# EZ_FX3USB.net
KiCad netlist of a schematic drawn in Altium Designer
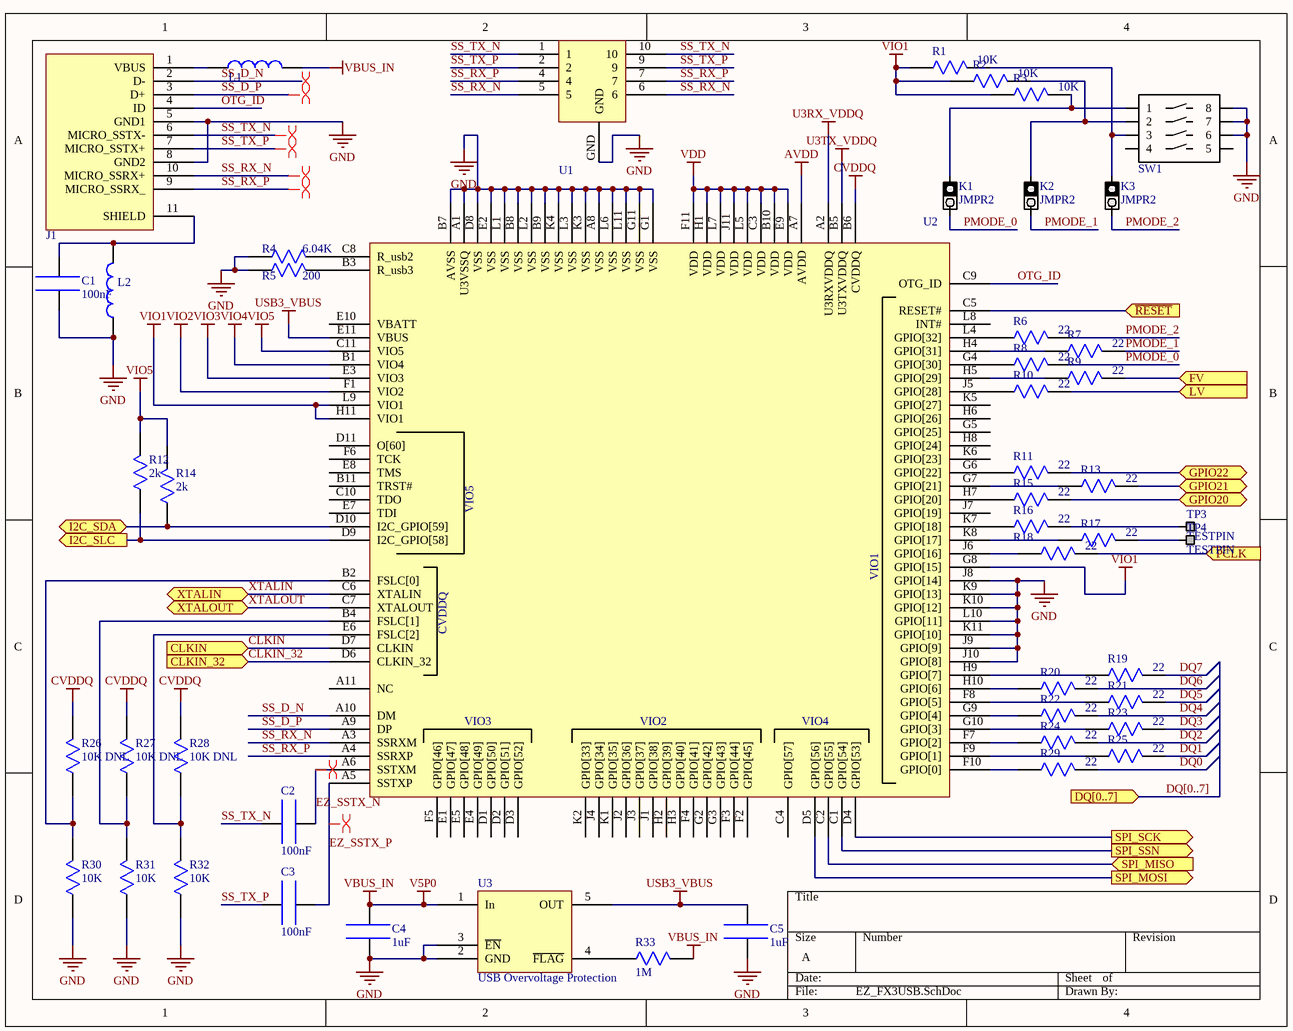
[diagram p0: EZ_FX3USB.SchDoc]

(export (version "E")
  (design (tool "Eeschema 10.0.6"))
  (components
    (comp (ref "C1")
      (value "100nF")
      (footprint "SMD Capacitor 0603")
      (fields (field (name "Comment") "Capacitor"))
      (libsource (lib "DA_Component_Library") (part "Capacitor"))
    )
    (comp (ref "C2")
      (value "100nF")
      (footprint "SMD Capacitor 0603")
      (fields (field (name "Comment") "Capacitor"))
      (libsource (lib "DA_Component_Library") (part "Capacitor"))
    )
    (comp (ref "C3")
      (value "100nF")
      (footprint "SMD Capacitor 0603")
      (fields (field (name "Comment") "Capacitor"))
      (libsource (lib "DA_Component_Library") (part "Capacitor"))
    )
    (comp (ref "C4")
      (value "1uF")
      (footprint "SMD Capacitor 0603")
      (fields (field (name "Comment") "Capacitor"))
      (libsource (lib "DA_Component_Library") (part "Capacitor"))
    )
    (comp (ref "C5")
      (value "1uF")
      (footprint "SMD Capacitor 0603")
      (fields (field (name "Comment") "Capacitor"))
      (libsource (lib "DA_Component_Library") (part "Capacitor"))
    )
    (comp (ref "J1")
      (value "USB3 MicroB")
      (footprint "PCBComponent_1")
      (libsource (lib "DA_Component_Library") (part "USB3 MicroB"))
    )
    (comp (ref "K1")
      (value "JMPR2")
      (footprint "JMPR2")
      (description "JMPR2 OPEN BY DEFAULT")
      (fields
        (field (name "MANUFACTURER") "Sullins Connector Solutions")
        (field (name "MANUFACTURER PART NUMBER") "PBC36SAAN")
      )
      (libsource (lib "vh_altium_library") (part "JMPR2"))
    )
    (comp (ref "K2")
      (value "JMPR2")
      (footprint "JMPR2")
      (description "JMPR2 OPEN BY DEFAULT")
      (fields
        (field (name "MANUFACTURER") "Sullins Connector Solutions")
        (field (name "MANUFACTURER PART NUMBER") "PBC36SAAN")
      )
      (libsource (lib "vh_altium_library") (part "JMPR2"))
    )
    (comp (ref "K3")
      (value "JMPR2")
      (footprint "JMPR2")
      (description "JMPR2 OPEN BY DEFAULT")
      (fields
        (field (name "MANUFACTURER") "Sullins Connector Solutions")
        (field (name "MANUFACTURER PART NUMBER") "PBC36SAAN")
      )
      (libsource (lib "vh_altium_library") (part "JMPR2"))
    )
    (comp (ref "L1")
      (value "Ferrite Bead")
      (footprint "BLM21PG221SN1D_0805")
      (libsource (lib "DA_Component_Library") (part "Ferrite Bead"))
    )
    (comp (ref "L2")
      (value "Ferrite Bead")
      (footprint "BLM21PG221SN1D_0805")
      (libsource (lib "DA_Component_Library") (part "Ferrite Bead"))
    )
    (comp (ref "R1")
      (value "10K")
      (footprint "SMD Resistor 0603")
      (libsource (lib "DA_Component_Library") (part "Resistor"))
    )
    (comp (ref "R2")
      (value "10K")
      (footprint "SMD Resistor 0603")
      (fields (field (name "Comment") "Resistor"))
      (libsource (lib "DA_Component_Library") (part "Resistor"))
    )
    (comp (ref "R3")
      (value "10K")
      (footprint "SMD Resistor 0603")
      (fields (field (name "Comment") "Resistor"))
      (libsource (lib "DA_Component_Library") (part "Resistor"))
    )
    (comp (ref "R4")
      (value "6.04K")
      (footprint "SMD Resistor 0603")
      (fields (field (name "Comment") "Resistor"))
      (libsource (lib "DA_Component_Library") (part "Resistor"))
    )
    (comp (ref "R5")
      (value "200")
      (footprint "SMD Resistor 0603")
      (fields (field (name "Comment") "Resistor"))
      (libsource (lib "DA_Component_Library") (part "Resistor"))
    )
    (comp (ref "R6")
      (value "22")
      (footprint "SMD Resistor 0603")
      (fields (field (name "Comment") "\"=Value\""))
      (libsource (lib "DA_Component_Library") (part "Resistor"))
    )
    (comp (ref "R7")
      (value "22")
      (footprint "SMD Resistor 0603")
      (fields (field (name "Comment") "Resistor"))
      (libsource (lib "DA_Component_Library") (part "Resistor"))
    )
    (comp (ref "R8")
      (value "22")
      (footprint "SMD Resistor 0603")
      (fields (field (name "Comment") "Resistor"))
      (libsource (lib "DA_Component_Library") (part "Resistor"))
    )
    (comp (ref "R9")
      (value "22")
      (footprint "SMD Resistor 0603")
      (fields (field (name "Comment") "Resistor"))
      (libsource (lib "DA_Component_Library") (part "Resistor"))
    )
    (comp (ref "R10")
      (value "22")
      (footprint "SMD Resistor 0603")
      (fields (field (name "Comment") "Resistor"))
      (libsource (lib "DA_Component_Library") (part "Resistor"))
    )
    (comp (ref "R11")
      (value "22")
      (footprint "SMD Resistor 0603")
      (fields (field (name "Comment") "Resistor"))
      (libsource (lib "DA_Component_Library") (part "Resistor"))
    )
    (comp (ref "R12")
      (value "2k")
      (footprint "SMD Resistor 0603")
      (fields (field (name "Comment") "Resistor"))
      (libsource (lib "DA_Component_Library") (part "Resistor"))
    )
    (comp (ref "R13")
      (value "22")
      (footprint "SMD Resistor 0603")
      (fields (field (name "Comment") "Resistor"))
      (libsource (lib "DA_Component_Library") (part "Resistor"))
    )
    (comp (ref "R14")
      (value "2k")
      (footprint "SMD Resistor 0603")
      (fields (field (name "Comment") "Resistor"))
      (libsource (lib "DA_Component_Library") (part "Resistor"))
    )
    (comp (ref "R15")
      (value "22")
      (footprint "SMD Resistor 0603")
      (fields (field (name "Comment") "Resistor"))
      (libsource (lib "DA_Component_Library") (part "Resistor"))
    )
    (comp (ref "R16")
      (value "22")
      (footprint "SMD Resistor 0603")
      (fields (field (name "Comment") "Resistor"))
      (libsource (lib "DA_Component_Library") (part "Resistor"))
    )
    (comp (ref "R17")
      (value "22")
      (footprint "SMD Resistor 0603")
      (fields (field (name "Comment") "Resistor"))
      (libsource (lib "DA_Component_Library") (part "Resistor"))
    )
    (comp (ref "R18")
      (value "22")
      (footprint "SMD Resistor 0603")
      (fields (field (name "Comment") "Resistor"))
      (libsource (lib "DA_Component_Library") (part "Resistor"))
    )
    (comp (ref "R19")
      (value "22")
      (footprint "SMD Resistor 0603")
      (fields (field (name "Comment") "Resistor"))
      (libsource (lib "DA_Component_Library") (part "Resistor"))
    )
    (comp (ref "R20")
      (value "22")
      (footprint "SMD Resistor 0603")
      (fields (field (name "Comment") "Resistor"))
      (libsource (lib "DA_Component_Library") (part "Resistor"))
    )
    (comp (ref "R21")
      (value "22")
      (footprint "SMD Resistor 0603")
      (fields (field (name "Comment") "Resistor"))
      (libsource (lib "DA_Component_Library") (part "Resistor"))
    )
    (comp (ref "R22")
      (value "22")
      (footprint "SMD Resistor 0603")
      (fields (field (name "Comment") "Resistor"))
      (libsource (lib "DA_Component_Library") (part "Resistor"))
    )
    (comp (ref "R23")
      (value "22")
      (footprint "SMD Resistor 0603")
      (fields (field (name "Comment") "Resistor"))
      (libsource (lib "DA_Component_Library") (part "Resistor"))
    )
    (comp (ref "R24")
      (value "22")
      (footprint "SMD Resistor 0603")
      (fields (field (name "Comment") "Resistor"))
      (libsource (lib "DA_Component_Library") (part "Resistor"))
    )
    (comp (ref "R25")
      (value "22")
      (footprint "SMD Resistor 0603")
      (fields (field (name "Comment") "Resistor"))
      (libsource (lib "DA_Component_Library") (part "Resistor"))
    )
    (comp (ref "R26")
      (value "10K DNL")
      (footprint "SMD Resistor 0603")
      (fields (field (name "Comment") "Resistor"))
      (libsource (lib "DA_Component_Library") (part "Resistor"))
    )
    (comp (ref "R27")
      (value "10K DNL")
      (footprint "SMD Resistor 0603")
      (fields (field (name "Comment") "Resistor"))
      (libsource (lib "DA_Component_Library") (part "Resistor"))
    )
    (comp (ref "R28")
      (value "10K DNL")
      (footprint "SMD Resistor 0603")
      (fields (field (name "Comment") "Resistor"))
      (libsource (lib "DA_Component_Library") (part "Resistor"))
    )
    (comp (ref "R29")
      (value "22")
      (footprint "SMD Resistor 0603")
      (fields (field (name "Comment") "Resistor"))
      (libsource (lib "DA_Component_Library") (part "Resistor"))
    )
    (comp (ref "R30")
      (value "10K")
      (footprint "SMD Resistor 0603")
      (fields (field (name "Comment") "Resistor"))
      (libsource (lib "DA_Component_Library") (part "Resistor"))
    )
    (comp (ref "R31")
      (value "10K")
      (footprint "SMD Resistor 0603")
      (fields (field (name "Comment") "Resistor"))
      (libsource (lib "DA_Component_Library") (part "Resistor"))
    )
    (comp (ref "R32")
      (value "10K")
      (footprint "SMD Resistor 0603")
      (fields (field (name "Comment") "Resistor"))
      (libsource (lib "DA_Component_Library") (part "Resistor"))
    )
    (comp (ref "R33")
      (value "1M")
      (footprint "SMD Resistor 0603")
      (fields (field (name "Comment") "Resistor"))
      (libsource (lib "DA_Component_Library") (part "Resistor"))
    )
    (comp (ref "SW1")
      (value "SW_DIP_4Position")
      (footprint "218-4LPST")
      (libsource (lib "DA_Component_Library") (part "SW_DIP_4Position"))
    )
    (comp (ref "TP3")
      (value "TESTPIN")
      (footprint "TESTPIN")
      (description "TESTPIN SINGLE PIN HEADER")
      (libsource (lib "vh_altium_library") (part "TESTPIN"))
    )
    (comp (ref "TP4")
      (value "TESTPIN")
      (footprint "TESTPIN")
      (description "TESTPIN SINGLE PIN HEADER")
      (libsource (lib "vh_altium_library") (part "TESTPIN"))
    )
    (comp (ref "U1")
      (value "ESD_4Channel")
      (footprint "SP3010-04UTG")
      (libsource (lib "DA_Component_Library") (part "ESD_4Channel"))
    )
    (comp (ref "U2")
      (value "EZ FX3 USB")
      (footprint "BGA121C80P11X11_1000X1000X100")
      (libsource (lib "DA_Component_Library") (part "EZ FX3 USB"))
    )
    (comp (ref "U3")
      (value "USB Overvoltage Protection")
      (footprint "TSOP-5 _ NCP361SNT1G")
      (libsource (lib "DA_Component_Library") (part "USB Overvoltage Protection"))
    )
  )
  (nets
    (net (code "1") (name "/CLKIN") (class "Default")
      (node (ref "U2") (pin "D7") (pinfunction "CLKIN_D7") (pintype "passive"))
    )
    (net (code "2") (name "/CLKIN_32") (class "Default")
      (node (ref "U2") (pin "D6") (pinfunction "CLKIN_32_D6") (pintype "passive"))
    )
    (net (code "3") (name "/DQ0") (class "Default")
      (node (ref "R29") (pin "1") (pinfunction "1_1") (pintype "passive"))
    )
    (net (code "4") (name "/DQ1") (class "Default")
      (node (ref "R25") (pin "1") (pinfunction "1_1") (pintype "passive"))
    )
    (net (code "5") (name "/DQ2") (class "Default")
      (node (ref "R24") (pin "1") (pinfunction "1_1") (pintype "passive"))
    )
    (net (code "6") (name "/DQ3") (class "Default")
      (node (ref "R23") (pin "1") (pinfunction "1_1") (pintype "passive"))
    )
    (net (code "7") (name "/DQ4") (class "Default")
      (node (ref "R22") (pin "1") (pinfunction "1_1") (pintype "passive"))
    )
    (net (code "8") (name "/DQ5") (class "Default")
      (node (ref "R21") (pin "1") (pinfunction "1_1") (pintype "passive"))
    )
    (net (code "9") (name "/DQ6") (class "Default")
      (node (ref "R20") (pin "1") (pinfunction "1_1") (pintype "passive"))
    )
    (net (code "10") (name "/DQ7") (class "Default")
      (node (ref "R19") (pin "1") (pinfunction "1_1") (pintype "passive"))
    )
    (net (code "12") (name "/EZ_SSTX_N") (class "Default")
      (node (ref "C2") (pin "1") (pinfunction "1_1") (pintype "passive"))
      (node (ref "U2") (pin "A6") (pinfunction "SSTXM_A6") (pintype "passive"))
    )
    (net (code "13") (name "/EZ_SSTX_P") (class "Default")
      (node (ref "C3") (pin "1") (pinfunction "1_1") (pintype "passive"))
      (node (ref "U2") (pin "A5") (pinfunction "SSTXP_A5") (pintype "passive"))
    )
    (net (code "14") (name "/FV") (class "Default")
      (node (ref "R9") (pin "1") (pinfunction "1_1") (pintype "passive"))
    )
    (net (code "15") (name "/GPIO20") (class "Default")
      (node (ref "R15") (pin "1") (pinfunction "1_1") (pintype "passive"))
    )
    (net (code "16") (name "/GPIO21") (class "Default")
      (node (ref "R13") (pin "1") (pinfunction "1_1") (pintype "passive"))
    )
    (net (code "17") (name "/GPIO22") (class "Default")
      (node (ref "R11") (pin "1") (pinfunction "1_1") (pintype "passive"))
    )
    (net (code "18") (name "/I2C_SDA") (class "Default")
      (node (ref "R14") (pin "0") (pinfunction "0_0") (pintype "passive"))
      (node (ref "U2") (pin "D10") (pinfunction "I2C_GPIO[59]_D10") (pintype "passive"))
    )
    (net (code "19") (name "/I2C_SLC") (class "Default")
      (node (ref "R12") (pin "0") (pinfunction "0_0") (pintype "passive"))
      (node (ref "U2") (pin "D9") (pinfunction "I2C_GPIO[58]_D9") (pintype "passive"))
    )
    (net (code "20") (name "/LV") (class "Default")
      (node (ref "R10") (pin "1") (pinfunction "1_1") (pintype "passive"))
    )
    (net (code "21") (name "/OTG_ID") (class "Default")
      (node (ref "J1") (pin "4") (pinfunction "ID_4") (pintype "passive"))
      (node (ref "U2") (pin "C9") (pinfunction "OTG_ID_C9") (pintype "passive"))
    )
    (net (code "22") (name "/PCLK") (class "Default")
      (node (ref "R18") (pin "1") (pinfunction "1_1") (pintype "passive"))
    )
    (net (code "23") (name "/PMODE_0") (class "Default")
      (node (ref "K1") (pin "2") (pintype "passive"))
      (node (ref "R8") (pin "1") (pinfunction "1_1") (pintype "passive"))
    )
    (net (code "24") (name "/PMODE_1") (class "Default")
      (node (ref "K2") (pin "2") (pintype "passive"))
      (node (ref "R7") (pin "1") (pinfunction "1_1") (pintype "passive"))
    )
    (net (code "25") (name "/PMODE_2") (class "Default")
      (node (ref "K3") (pin "2") (pintype "passive"))
      (node (ref "R6") (pin "1") (pinfunction "1_1") (pintype "passive"))
    )
    (net (code "26") (name "/SPI_MISO") (class "Default")
      (node (ref "U2") (pin "C2") (pinfunction "GPIO[55]_C2") (pintype "passive"))
    )
    (net (code "27") (name "/SPI_MOSI") (class "Default")
      (node (ref "U2") (pin "D5") (pinfunction "GPIO[56]_D5") (pintype "passive"))
    )
    (net (code "28") (name "/SPI_SCK") (class "Default")
      (node (ref "U2") (pin "D4") (pinfunction "GPIO[53]_D4") (pintype "passive"))
    )
    (net (code "29") (name "/SPI_SSN") (class "Default")
      (node (ref "U2") (pin "C1") (pinfunction "GPIO[54]_C1") (pintype "passive"))
    )
    (net (code "30") (name "/SS_D_N") (class "Default")
      (node (ref "J1") (pin "2") (pinfunction "D-_2") (pintype "passive"))
      (node (ref "U2") (pin "A10") (pinfunction "DM_A10") (pintype "passive"))
    )
    (net (code "31") (name "/SS_D_P") (class "Default")
      (node (ref "J1") (pin "3") (pinfunction "D+_3") (pintype "passive"))
      (node (ref "U2") (pin "A9") (pinfunction "DP_A9") (pintype "passive"))
    )
    (net (code "32") (name "/SS_RX_N") (class "Default")
      (node (ref "J1") (pin "10") (pinfunction "MICRO_SSRX+_10") (pintype "passive"))
      (node (ref "U1") (pin "5") (pinfunction "5_5") (pintype "passive"))
      (node (ref "U1") (pin "6") (pinfunction "6_6") (pintype "passive"))
      (node (ref "U2") (pin "A3") (pinfunction "SSRXM_A3") (pintype "passive"))
    )
    (net (code "33") (name "/SS_RX_P") (class "Default")
      (node (ref "J1") (pin "9") (pinfunction "MICRO_SSRX__9") (pintype "passive"))
      (node (ref "U1") (pin "4") (pinfunction "4_4") (pintype "passive"))
      (node (ref "U1") (pin "7") (pinfunction "7_7") (pintype "passive"))
      (node (ref "U2") (pin "A4") (pinfunction "SSRXP_A4") (pintype "passive"))
    )
    (net (code "34") (name "/SS_TX_N") (class "Default")
      (node (ref "C2") (pin "0") (pinfunction "0_0") (pintype "passive"))
      (node (ref "J1") (pin "6") (pinfunction "MICRO_SSTX-_6") (pintype "passive"))
      (node (ref "U1") (pin "1") (pinfunction "1_1") (pintype "passive"))
      (node (ref "U1") (pin "10") (pinfunction "10_10") (pintype "passive"))
    )
    (net (code "35") (name "/SS_TX_P") (class "Default")
      (node (ref "C3") (pin "0") (pinfunction "0_0") (pintype "passive"))
      (node (ref "J1") (pin "7") (pinfunction "MICRO_SSTX+_7") (pintype "passive"))
      (node (ref "U1") (pin "2") (pinfunction "2_2") (pintype "passive"))
      (node (ref "U1") (pin "9") (pinfunction "9_9") (pintype "passive"))
    )
    (net (code "36") (name "/XTALIN") (class "Default")
      (node (ref "U2") (pin "C6") (pinfunction "XTALIN_C6") (pintype "passive"))
    )
    (net (code "37") (name "/XTALOUT") (class "Default")
      (node (ref "U2") (pin "C7") (pinfunction "XTALOUT_C7") (pintype "passive"))
    )
    (net (code "38") (name "/~{RESET}") (class "Default")
      (node (ref "U2") (pin "C5") (pinfunction "RESET#_C5") (pintype "passive"))
    )
    (net (code "39") (name "AVDD") (class "Default")
      (node (ref "U2") (pin "A7") (pinfunction "AVDD_A7") (pintype "passive"))
    )
    (net (code "40") (name "CVDDQ") (class "Default")
      (node (ref "R26") (pin "1") (pinfunction "1_1") (pintype "passive"))
      (node (ref "R27") (pin "1") (pinfunction "1_1") (pintype "passive"))
      (node (ref "R28") (pin "1") (pinfunction "1_1") (pintype "passive"))
      (node (ref "U2") (pin "B6") (pinfunction "CVDDQ_B6") (pintype "passive"))
    )
    (net (code "41") (name "GND") (class "Default")
      (node (ref "C1") (pin "0") (pinfunction "0_0") (pintype "passive"))
      (node (ref "C4") (pin "0") (pinfunction "0_0") (pintype "passive"))
      (node (ref "C5") (pin "0") (pinfunction "0_0") (pintype "passive"))
      (node (ref "J1") (pin "5") (pinfunction "GND1_5") (pintype "passive"))
      (node (ref "J1") (pin "8") (pinfunction "GND2_8") (pintype "passive"))
      (node (ref "L2") (pin "1") (pinfunction "1_1") (pintype "passive"))
      (node (ref "R30") (pin "0") (pinfunction "0_0") (pintype "passive"))
      (node (ref "R31") (pin "0") (pinfunction "0_0") (pintype "passive"))
      (node (ref "R32") (pin "0") (pinfunction "0_0") (pintype "passive"))
      (node (ref "R4") (pin "0") (pinfunction "0_0") (pintype "passive"))
      (node (ref "R5") (pin "0") (pinfunction "0_0") (pintype "passive"))
      (node (ref "SW1") (pin "6") (pinfunction "6_6") (pintype "passive"))
      (node (ref "SW1") (pin "7") (pinfunction "7_7") (pintype "passive"))
      (node (ref "SW1") (pin "8") (pinfunction "8_8") (pintype "passive"))
      (node (ref "U1") (pin "GND") (pinfunction "GND_GND") (pintype "passive"))
      (node (ref "U2") (pin "A1") (pinfunction "U3VSSQ_A1") (pintype "passive"))
      (node (ref "U2") (pin "A8") (pinfunction "VSS_A8") (pintype "passive"))
      (node (ref "U2") (pin "B7") (pinfunction "AVSS_B7") (pintype "passive"))
      (node (ref "U2") (pin "B8") (pinfunction "VSS_B8") (pintype "passive"))
      (node (ref "U2") (pin "B9") (pinfunction "VSS_B9") (pintype "passive"))
      (node (ref "U2") (pin "D8") (pinfunction "VSS_D8") (pintype "passive"))
      (node (ref "U2") (pin "E2") (pinfunction "VSS_E2") (pintype "passive"))
      (node (ref "U2") (pin "G1") (pinfunction "VSS_G1") (pintype "passive"))
      (node (ref "U2") (pin "G11") (pinfunction "VSS_G11") (pintype "passive"))
      (node (ref "U2") (pin "J10") (pinfunction "GPIO[8]_J10") (pintype "passive"))
      (node (ref "U2") (pin "J8") (pinfunction "GPIO[14]_J8") (pintype "passive"))
      (node (ref "U2") (pin "J9") (pinfunction "GPIO[9]_J9") (pintype "passive"))
      (node (ref "U2") (pin "K10") (pinfunction "GPIO[12]_K10") (pintype "passive"))
      (node (ref "U2") (pin "K11") (pinfunction "GPIO[10]_K11") (pintype "passive"))
      (node (ref "U2") (pin "K3") (pinfunction "VSS_K3") (pintype "passive"))
      (node (ref "U2") (pin "K4") (pinfunction "VSS_K4") (pintype "passive"))
      (node (ref "U2") (pin "K9") (pinfunction "GPIO[13]_K9") (pintype "passive"))
      (node (ref "U2") (pin "L1") (pinfunction "VSS_L1") (pintype "passive"))
      (node (ref "U2") (pin "L10") (pinfunction "GPIO[11]_L10") (pintype "passive"))
      (node (ref "U2") (pin "L11") (pinfunction "VSS_L11") (pintype "passive"))
      (node (ref "U2") (pin "L2") (pinfunction "VSS_L2") (pintype "passive"))
      (node (ref "U2") (pin "L3") (pinfunction "VSS_L3") (pintype "passive"))
      (node (ref "U2") (pin "L6") (pinfunction "VSS_L6") (pintype "passive"))
      (node (ref "U3") (pin "2") (pinfunction "GND_2") (pintype "passive"))
      (node (ref "U3") (pin "3") (pinfunction "~{EN}_3") (pintype "passive"))
    )
    (net (code "42") (name "Net-(J1-SHIELD)") (class "Default")
      (node (ref "C1") (pin "1") (pinfunction "1_1") (pintype "passive"))
      (node (ref "J1") (pin "11") (pinfunction "SHIELD_11") (pintype "passive"))
      (node (ref "L2") (pin "2") (pinfunction "2_2") (pintype "passive"))
    )
    (net (code "43") (name "Net-(J1-VBUS)") (class "Default")
      (node (ref "J1") (pin "1") (pinfunction "VBUS_1") (pintype "passive"))
      (node (ref "L1") (pin "1") (pinfunction "1_1") (pintype "passive"))
    )
    (net (code "44") (name "Net-(K1-Pad1)") (class "Default")
      (node (ref "K1") (pin "1") (pintype "passive"))
      (node (ref "R3") (pin "1") (pinfunction "1_1") (pintype "passive"))
      (node (ref "SW1") (pin "1") (pinfunction "1_1") (pintype "passive"))
    )
    (net (code "45") (name "Net-(K2-Pad1)") (class "Default")
      (node (ref "K2") (pin "1") (pintype "passive"))
      (node (ref "R2") (pin "1") (pinfunction "1_1") (pintype "passive"))
      (node (ref "SW1") (pin "2") (pinfunction "2_2") (pintype "passive"))
    )
    (net (code "46") (name "Net-(K3-Pad1)") (class "Default")
      (node (ref "K3") (pin "1") (pintype "passive"))
      (node (ref "R1") (pin "1") (pinfunction "1_1") (pintype "passive"))
      (node (ref "SW1") (pin "3") (pinfunction "3_3") (pintype "passive"))
    )
    (net (code "47") (name "Net-(R16-Pad1)") (class "Default")
      (node (ref "R16") (pin "1") (pinfunction "1_1") (pintype "passive"))
      (node (ref "TP3") (pin "1") (pinfunction "1_1") (pintype "passive"))
    )
    (net (code "48") (name "Net-(R17-Pad1)") (class "Default")
      (node (ref "R17") (pin "1") (pinfunction "1_1") (pintype "passive"))
      (node (ref "TP4") (pin "1") (pinfunction "1_1") (pintype "passive"))
    )
    (net (code "49") (name "Net-(U2-FSLC[0])") (class "Default")
      (node (ref "R26") (pin "0") (pinfunction "0_0") (pintype "passive"))
      (node (ref "R30") (pin "1") (pinfunction "1_1") (pintype "passive"))
      (node (ref "U2") (pin "B2") (pinfunction "FSLC[0]_B2") (pintype "passive"))
    )
    (net (code "50") (name "Net-(U2-FSLC[1])") (class "Default")
      (node (ref "R27") (pin "0") (pinfunction "0_0") (pintype "passive"))
      (node (ref "R31") (pin "1") (pinfunction "1_1") (pintype "passive"))
      (node (ref "U2") (pin "B4") (pinfunction "FSLC[1]_B4") (pintype "passive"))
    )
    (net (code "51") (name "Net-(U2-FSLC[2])") (class "Default")
      (node (ref "R28") (pin "0") (pinfunction "0_0") (pintype "passive"))
      (node (ref "R32") (pin "1") (pinfunction "1_1") (pintype "passive"))
      (node (ref "U2") (pin "E6") (pinfunction "FSLC[2]_E6") (pintype "passive"))
    )
    (net (code "52") (name "Net-(U2-GPIO[0])") (class "Default")
      (node (ref "R29") (pin "0") (pinfunction "0_0") (pintype "passive"))
      (node (ref "U2") (pin "F10") (pinfunction "GPIO[0]_F10") (pintype "passive"))
    )
    (net (code "53") (name "Net-(U2-GPIO[1])") (class "Default")
      (node (ref "R25") (pin "0") (pinfunction "0_0") (pintype "passive"))
      (node (ref "U2") (pin "F9") (pinfunction "GPIO[1]_F9") (pintype "passive"))
    )
    (net (code "54") (name "Net-(U2-GPIO[2])") (class "Default")
      (node (ref "R24") (pin "0") (pinfunction "0_0") (pintype "passive"))
      (node (ref "U2") (pin "F7") (pinfunction "GPIO[2]_F7") (pintype "passive"))
    )
    (net (code "55") (name "Net-(U2-GPIO[3])") (class "Default")
      (node (ref "R23") (pin "0") (pinfunction "0_0") (pintype "passive"))
      (node (ref "U2") (pin "G10") (pinfunction "GPIO[3]_G10") (pintype "passive"))
    )
    (net (code "56") (name "Net-(U2-GPIO[4])") (class "Default")
      (node (ref "R22") (pin "0") (pinfunction "0_0") (pintype "passive"))
      (node (ref "U2") (pin "G9") (pinfunction "GPIO[4]_G9") (pintype "passive"))
    )
    (net (code "57") (name "Net-(U2-GPIO[5])") (class "Default")
      (node (ref "R21") (pin "0") (pinfunction "0_0") (pintype "passive"))
      (node (ref "U2") (pin "F8") (pinfunction "GPIO[5]_F8") (pintype "passive"))
    )
    (net (code "58") (name "Net-(U2-GPIO[6])") (class "Default")
      (node (ref "R20") (pin "0") (pinfunction "0_0") (pintype "passive"))
      (node (ref "U2") (pin "H10") (pinfunction "GPIO[6]_H10") (pintype "passive"))
    )
    (net (code "59") (name "Net-(U2-GPIO[7])") (class "Default")
      (node (ref "R19") (pin "0") (pinfunction "0_0") (pintype "passive"))
      (node (ref "U2") (pin "H9") (pinfunction "GPIO[7]_H9") (pintype "passive"))
    )
    (net (code "60") (name "Net-(U2-GPIO[16])") (class "Default")
      (node (ref "R18") (pin "0") (pinfunction "0_0") (pintype "passive"))
      (node (ref "U2") (pin "J6") (pinfunction "GPIO[16]_J6") (pintype "passive"))
    )
    (net (code "61") (name "Net-(U2-GPIO[17])") (class "Default")
      (node (ref "R17") (pin "0") (pinfunction "0_0") (pintype "passive"))
      (node (ref "U2") (pin "K8") (pinfunction "GPIO[17]_K8") (pintype "passive"))
    )
    (net (code "62") (name "Net-(U2-GPIO[18])") (class "Default")
      (node (ref "R16") (pin "0") (pinfunction "0_0") (pintype "passive"))
      (node (ref "U2") (pin "K7") (pinfunction "GPIO[18]_K7") (pintype "passive"))
    )
    (net (code "63") (name "Net-(U2-GPIO[20])") (class "Default")
      (node (ref "R15") (pin "0") (pinfunction "0_0") (pintype "passive"))
      (node (ref "U2") (pin "H7") (pinfunction "GPIO[20]_H7") (pintype "passive"))
    )
    (net (code "64") (name "Net-(U2-GPIO[21])") (class "Default")
      (node (ref "R13") (pin "0") (pinfunction "0_0") (pintype "passive"))
      (node (ref "U2") (pin "G7") (pinfunction "GPIO[21]_G7") (pintype "passive"))
    )
    (net (code "65") (name "Net-(U2-GPIO[22])") (class "Default")
      (node (ref "R11") (pin "0") (pinfunction "0_0") (pintype "passive"))
      (node (ref "U2") (pin "G6") (pinfunction "GPIO[22]_G6") (pintype "passive"))
    )
    (net (code "66") (name "Net-(U2-GPIO[28])") (class "Default")
      (node (ref "R10") (pin "0") (pinfunction "0_0") (pintype "passive"))
      (node (ref "U2") (pin "J5") (pinfunction "GPIO[28]_J5") (pintype "passive"))
    )
    (net (code "67") (name "Net-(U2-GPIO[29])") (class "Default")
      (node (ref "R9") (pin "0") (pinfunction "0_0") (pintype "passive"))
      (node (ref "U2") (pin "H5") (pinfunction "GPIO[29]_H5") (pintype "passive"))
    )
    (net (code "68") (name "Net-(U2-GPIO[30])") (class "Default")
      (node (ref "R8") (pin "0") (pinfunction "0_0") (pintype "passive"))
      (node (ref "U2") (pin "G4") (pinfunction "GPIO[30]_G4") (pintype "passive"))
    )
    (net (code "69") (name "Net-(U2-GPIO[31])") (class "Default")
      (node (ref "R7") (pin "0") (pinfunction "0_0") (pintype "passive"))
      (node (ref "U2") (pin "H4") (pinfunction "GPIO[31]_H4") (pintype "passive"))
    )
    (net (code "70") (name "Net-(U2-GPIO[32])") (class "Default")
      (node (ref "R6") (pin "0") (pinfunction "0_0") (pintype "passive"))
      (node (ref "U2") (pin "L4") (pinfunction "GPIO[32]_L4") (pintype "passive"))
    )
    (net (code "71") (name "Net-(U2-R_usb2)") (class "Default")
      (node (ref "R4") (pin "1") (pinfunction "1_1") (pintype "passive"))
      (node (ref "U2") (pin "C8") (pinfunction "R_usb2_C8") (pintype "passive"))
    )
    (net (code "72") (name "Net-(U2-R_usb3)") (class "Default")
      (node (ref "R5") (pin "1") (pinfunction "1_1") (pintype "passive"))
      (node (ref "U2") (pin "B3") (pinfunction "R_usb3_B3") (pintype "passive"))
    )
    (net (code "73") (name "Net-(U3-~{FLAG})") (class "Default")
      (node (ref "R33") (pin "0") (pinfunction "0_0") (pintype "passive"))
      (node (ref "U3") (pin "4") (pinfunction "~{FLAG}_4") (pintype "passive"))
    )
    (net (code "74") (name "U3RX_VDDQ") (class "Default")
      (node (ref "U2") (pin "A2") (pinfunction "U3RXVDDQ_A2") (pintype "passive"))
    )
    (net (code "75") (name "U3TX_VDDQ") (class "Default")
      (node (ref "U2") (pin "B5") (pinfunction "U3TXVDDQ_B5") (pintype "passive"))
    )
    (net (code "76") (name "USB3_VBUS") (class "Default")
      (node (ref "C5") (pin "1") (pinfunction "1_1") (pintype "passive"))
      (node (ref "U2") (pin "E11") (pinfunction "VBUS_E11") (pintype "passive"))
      (node (ref "U3") (pin "5") (pinfunction "OUT_5") (pintype "passive"))
    )
    (net (code "77") (name "V5P0") (class "Default")
      (node (ref "C4") (pin "1") (pinfunction "1_1") (pintype "passive"))
      (node (ref "L1") (pin "2") (pinfunction "2_2") (pintype "passive"))
      (node (ref "R33") (pin "1") (pinfunction "1_1") (pintype "passive"))
      (node (ref "U3") (pin "1") (pinfunction "In_1") (pintype "passive"))
    )
    (net (code "78") (name "VDD") (class "Default")
      (node (ref "U2") (pin "B10") (pinfunction "VDD_B10") (pintype "passive"))
      (node (ref "U2") (pin "C3") (pinfunction "VDD_C3") (pintype "passive"))
      (node (ref "U2") (pin "E9") (pinfunction "VDD_E9") (pintype "passive"))
      (node (ref "U2") (pin "F11") (pinfunction "VDD_F11") (pintype "passive"))
      (node (ref "U2") (pin "H1") (pinfunction "VDD_H1") (pintype "passive"))
      (node (ref "U2") (pin "J11") (pinfunction "VDD_J11") (pintype "passive"))
      (node (ref "U2") (pin "L5") (pinfunction "VDD_L5") (pintype "passive"))
      (node (ref "U2") (pin "L7") (pinfunction "VDD_L7") (pintype "passive"))
    )
    (net (code "79") (name "VIO1") (class "Default")
      (node (ref "R1") (pin "0") (pinfunction "0_0") (pintype "passive"))
      (node (ref "R2") (pin "0") (pinfunction "0_0") (pintype "passive"))
      (node (ref "R3") (pin "0") (pinfunction "0_0") (pintype "passive"))
      (node (ref "U2") (pin "G8") (pinfunction "GPIO[15]_G8") (pintype "passive"))
      (node (ref "U2") (pin "H11") (pinfunction "VIO1_H11") (pintype "passive"))
      (node (ref "U2") (pin "L9") (pinfunction "VIO1_L9") (pintype "passive"))
    )
    (net (code "80") (name "VIO2") (class "Default")
      (node (ref "U2") (pin "F1") (pinfunction "VIO2_F1") (pintype "passive"))
    )
    (net (code "81") (name "VIO3") (class "Default")
      (node (ref "U2") (pin "E3") (pinfunction "VIO3_E3") (pintype "passive"))
    )
    (net (code "82") (name "VIO4") (class "Default")
      (node (ref "U2") (pin "B1") (pinfunction "VIO4_B1") (pintype "passive"))
    )
    (net (code "83") (name "VIO5") (class "Default")
      (node (ref "R12") (pin "1") (pinfunction "1_1") (pintype "passive"))
      (node (ref "R14") (pin "1") (pinfunction "1_1") (pintype "passive"))
      (node (ref "U2") (pin "C11") (pinfunction "VIO5_C11") (pintype "passive"))
    )
    (net (code "84") (name "unconnected-(SW1-Pad4)") (class "Default")
      (node (ref "SW1") (pin "4") (pinfunction "4_4") (pintype "passive"))
    )
    (net (code "85") (name "unconnected-(SW1-Pad5)") (class "Default")
      (node (ref "SW1") (pin "5") (pinfunction "5_5") (pintype "passive"))
    )
    (net (code "86") (name "unconnected-(U2-GPIO[19]-PadJ7)") (class "Default")
      (node (ref "U2") (pin "J7") (pinfunction "GPIO[19]_J7") (pintype "passive"))
    )
    (net (code "87") (name "unconnected-(U2-GPIO[23]-PadK6)") (class "Default")
      (node (ref "U2") (pin "K6") (pinfunction "GPIO[23]_K6") (pintype "passive"))
    )
    (net (code "88") (name "unconnected-(U2-GPIO[24]-PadH8)") (class "Default")
      (node (ref "U2") (pin "H8") (pinfunction "GPIO[24]_H8") (pintype "passive"))
    )
    (net (code "89") (name "unconnected-(U2-GPIO[25]-PadG5)") (class "Default")
      (node (ref "U2") (pin "G5") (pinfunction "GPIO[25]_G5") (pintype "passive"))
    )
    (net (code "90") (name "unconnected-(U2-GPIO[26]-PadH6)") (class "Default")
      (node (ref "U2") (pin "H6") (pinfunction "GPIO[26]_H6") (pintype "passive"))
    )
    (net (code "91") (name "unconnected-(U2-GPIO[27]-PadK5)") (class "Default")
      (node (ref "U2") (pin "K5") (pinfunction "GPIO[27]_K5") (pintype "passive"))
    )
    (net (code "92") (name "unconnected-(U2-GPIO[33]-PadK2)") (class "Default")
      (node (ref "U2") (pin "K2") (pinfunction "GPIO[33]_K2") (pintype "passive"))
    )
    (net (code "93") (name "unconnected-(U2-GPIO[34]-PadJ4)") (class "Default")
      (node (ref "U2") (pin "J4") (pinfunction "GPIO[34]_J4") (pintype "passive"))
    )
    (net (code "94") (name "unconnected-(U2-GPIO[35]-PadK1)") (class "Default")
      (node (ref "U2") (pin "K1") (pinfunction "GPIO[35]_K1") (pintype "passive"))
    )
    (net (code "95") (name "unconnected-(U2-GPIO[36]-PadJ2)") (class "Default")
      (node (ref "U2") (pin "J2") (pinfunction "GPIO[36]_J2") (pintype "passive"))
    )
    (net (code "96") (name "unconnected-(U2-GPIO[37]-PadJ3)") (class "Default")
      (node (ref "U2") (pin "J3") (pinfunction "GPIO[37]_J3") (pintype "passive"))
    )
    (net (code "97") (name "unconnected-(U2-GPIO[38]-PadJ1)") (class "Default")
      (node (ref "U2") (pin "J1") (pinfunction "GPIO[38]_J1") (pintype "passive"))
    )
    (net (code "98") (name "unconnected-(U2-GPIO[39]-PadH2)") (class "Default")
      (node (ref "U2") (pin "H2") (pinfunction "GPIO[39]_H2") (pintype "passive"))
    )
    (net (code "99") (name "unconnected-(U2-GPIO[40]-PadH3)") (class "Default")
      (node (ref "U2") (pin "H3") (pinfunction "GPIO[40]_H3") (pintype "passive"))
    )
    (net (code "100") (name "unconnected-(U2-GPIO[41]-PadF4)") (class "Default")
      (node (ref "U2") (pin "F4") (pinfunction "GPIO[41]_F4") (pintype "passive"))
    )
    (net (code "101") (name "unconnected-(U2-GPIO[42]-PadG2)") (class "Default")
      (node (ref "U2") (pin "G2") (pinfunction "GPIO[42]_G2") (pintype "passive"))
    )
    (net (code "102") (name "unconnected-(U2-GPIO[43]-PadG3)") (class "Default")
      (node (ref "U2") (pin "G3") (pinfunction "GPIO[43]_G3") (pintype "passive"))
    )
    (net (code "103") (name "unconnected-(U2-GPIO[44]-PadF3)") (class "Default")
      (node (ref "U2") (pin "F3") (pinfunction "GPIO[44]_F3") (pintype "passive"))
    )
    (net (code "104") (name "unconnected-(U2-GPIO[45]-PadF2)") (class "Default")
      (node (ref "U2") (pin "F2") (pinfunction "GPIO[45]_F2") (pintype "passive"))
    )
    (net (code "105") (name "unconnected-(U2-GPIO[46]-PadF5)") (class "Default")
      (node (ref "U2") (pin "F5") (pinfunction "GPIO[46]_F5") (pintype "passive"))
    )
    (net (code "106") (name "unconnected-(U2-GPIO[47]-PadE1)") (class "Default")
      (node (ref "U2") (pin "E1") (pinfunction "GPIO[47]_E1") (pintype "passive"))
    )
    (net (code "107") (name "unconnected-(U2-GPIO[48]-PadE5)") (class "Default")
      (node (ref "U2") (pin "E5") (pinfunction "GPIO[48]_E5") (pintype "passive"))
    )
    (net (code "108") (name "unconnected-(U2-GPIO[49]-PadE4)") (class "Default")
      (node (ref "U2") (pin "E4") (pinfunction "GPIO[49]_E4") (pintype "passive"))
    )
    (net (code "109") (name "unconnected-(U2-GPIO[50]-PadD1)") (class "Default")
      (node (ref "U2") (pin "D1") (pinfunction "GPIO[50]_D1") (pintype "passive"))
    )
    (net (code "110") (name "unconnected-(U2-GPIO[51]-PadD2)") (class "Default")
      (node (ref "U2") (pin "D2") (pinfunction "GPIO[51]_D2") (pintype "passive"))
    )
    (net (code "111") (name "unconnected-(U2-GPIO[52]-PadD3)") (class "Default")
      (node (ref "U2") (pin "D3") (pinfunction "GPIO[52]_D3") (pintype "passive"))
    )
    (net (code "112") (name "unconnected-(U2-GPIO[57]-PadC4)") (class "Default")
      (node (ref "U2") (pin "C4") (pinfunction "GPIO[57]_C4") (pintype "passive"))
    )
    (net (code "113") (name "unconnected-(U2-INT#-PadL8)") (class "Default")
      (node (ref "U2") (pin "L8") (pinfunction "INT#_L8") (pintype "passive"))
    )
    (net (code "114") (name "unconnected-(U2-NC-PadA11)") (class "Default")
      (node (ref "U2") (pin "A11") (pinfunction "NC_A11") (pintype "passive"))
    )
    (net (code "115") (name "unconnected-(U2-O[60]-PadD11)") (class "Default")
      (node (ref "U2") (pin "D11") (pinfunction "O[60]_D11") (pintype "passive"))
    )
    (net (code "116") (name "unconnected-(U2-TCK-PadF6)") (class "Default")
      (node (ref "U2") (pin "F6") (pinfunction "TCK_F6") (pintype "passive"))
    )
    (net (code "117") (name "unconnected-(U2-TDI-PadE7)") (class "Default")
      (node (ref "U2") (pin "E7") (pinfunction "TDI_E7") (pintype "passive"))
    )
    (net (code "118") (name "unconnected-(U2-TDO-PadC10)") (class "Default")
      (node (ref "U2") (pin "C10") (pinfunction "TDO_C10") (pintype "passive"))
    )
    (net (code "119") (name "unconnected-(U2-TMS-PadE8)") (class "Default")
      (node (ref "U2") (pin "E8") (pinfunction "TMS_E8") (pintype "passive"))
    )
    (net (code "120") (name "unconnected-(U2-TRST#-PadB11)") (class "Default")
      (node (ref "U2") (pin "B11") (pinfunction "TRST#_B11") (pintype "passive"))
    )
    (net (code "121") (name "unconnected-(U2-VBATT-PadE10)") (class "Default")
      (node (ref "U2") (pin "E10") (pinfunction "VBATT_E10") (pintype "passive"))
    )
  )
)
